# logicBlocks-NOT.net
KiCad netlist of a schematic drawn in EAGLE
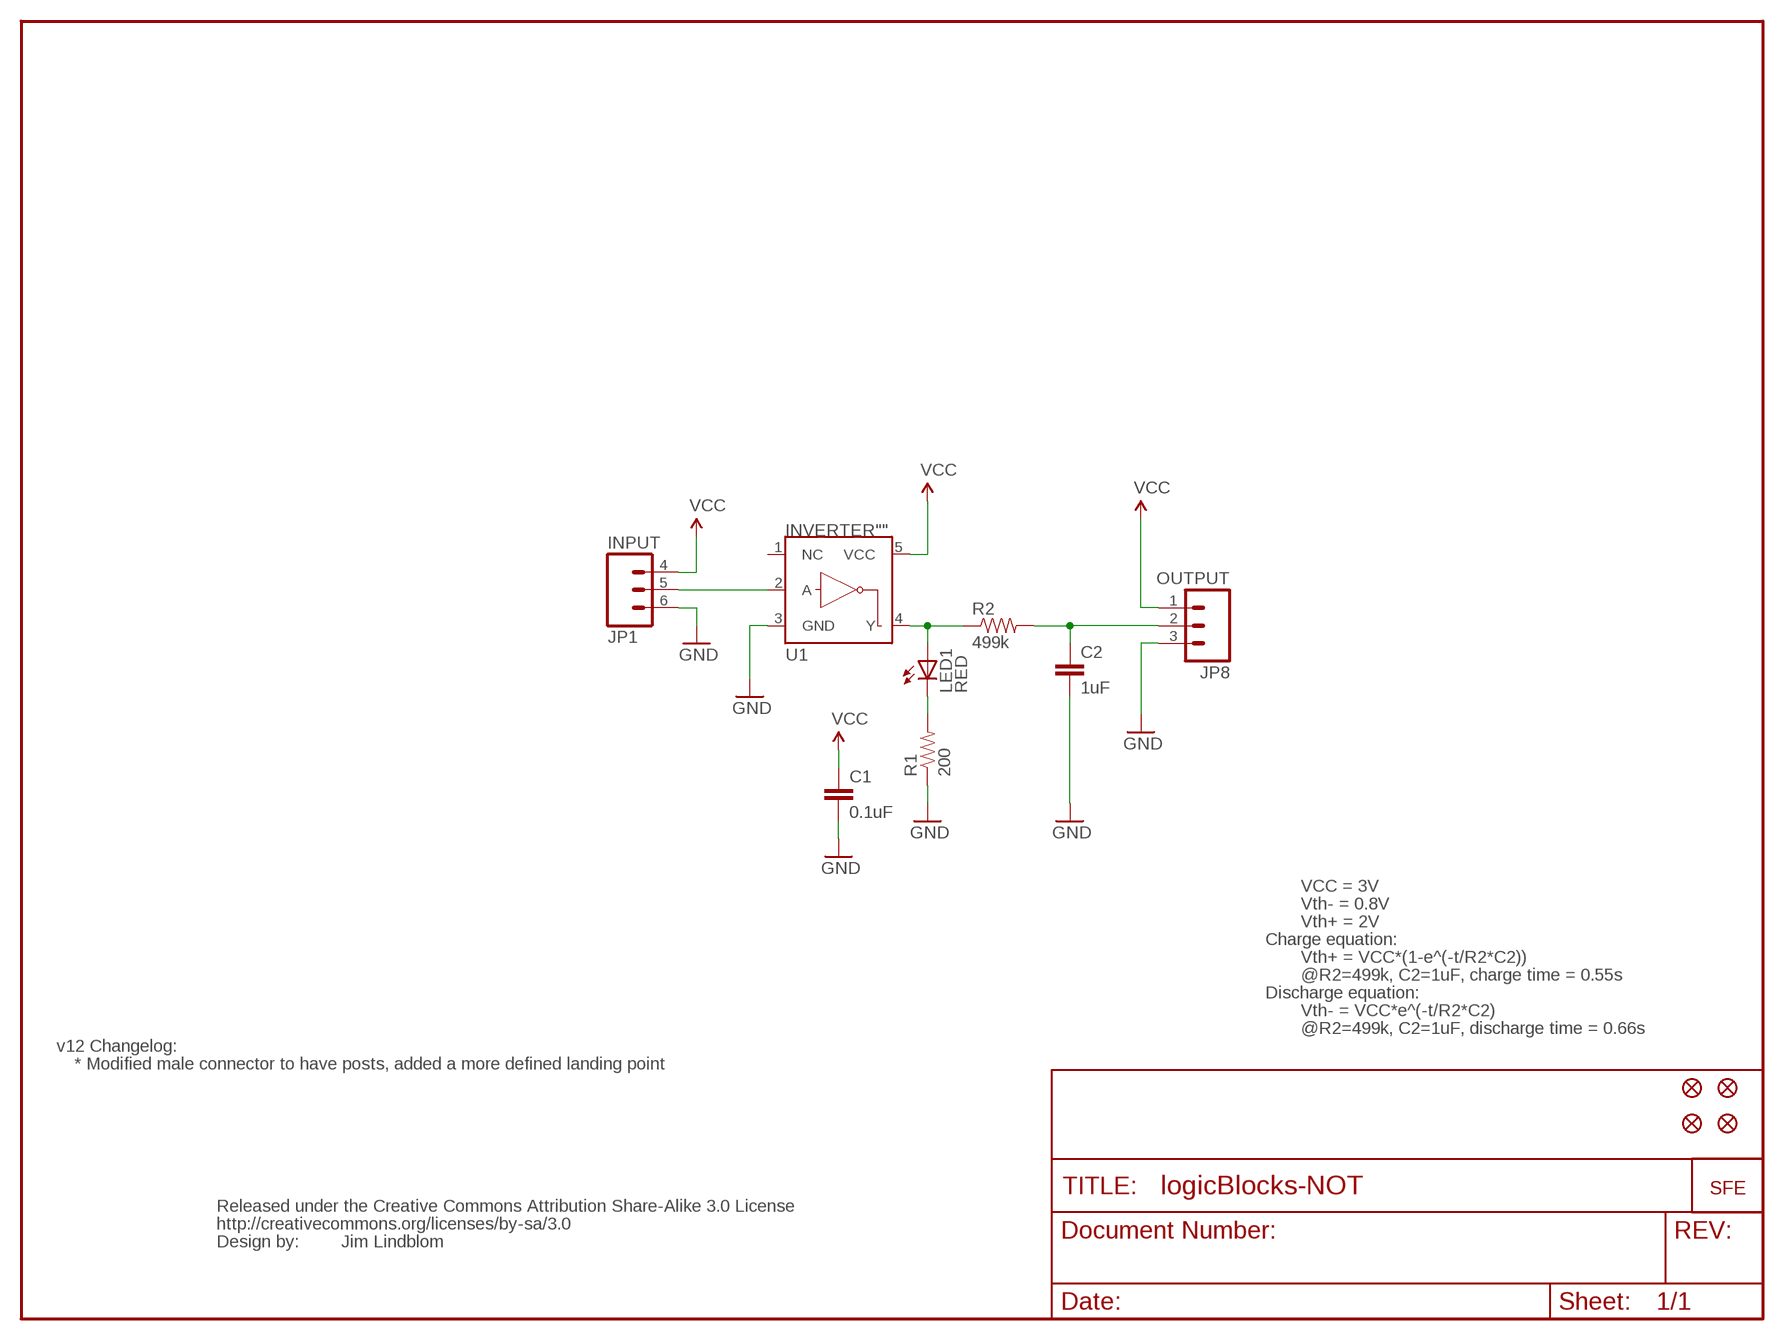
[diagram p0: schematic, sheet 1]

(export (version "E")
  (design (tool "Eeschema 10.0.6"))
  (components
    (comp (ref "C1")
      (value "0.1uF")
      (footprint "eagle-import:0402-CAP")
      (libsource (lib "eagle-import") (part "CAP0402-CAP"))
    )
    (comp (ref "C2")
      (value "1uF")
      (footprint "eagle-import:0402-CAP")
      (libsource (lib "eagle-import") (part "CAP0402-CAP"))
    )
    (comp (ref "FID1")
      (value "FIDUCIAL1X2")
      (footprint "eagle-import:FIDUCIAL-1X2")
      (libsource (lib "eagle-import") (part "FIDUCIAL1X2"))
    )
    (comp (ref "FID2")
      (value "FIDUCIAL1X2")
      (footprint "eagle-import:FIDUCIAL-1X2")
      (libsource (lib "eagle-import") (part "FIDUCIAL1X2"))
    )
    (comp (ref "FID3")
      (value "FIDUCIAL1X2")
      (footprint "eagle-import:FIDUCIAL-1X2")
      (libsource (lib "eagle-import") (part "FIDUCIAL1X2"))
    )
    (comp (ref "FID4")
      (value "FIDUCIAL1X2")
      (footprint "eagle-import:FIDUCIAL-1X2")
      (libsource (lib "eagle-import") (part "FIDUCIAL1X2"))
    )
    (comp (ref "JP1")
      (value "INPUT")
      (footprint "eagle-import:1X03-SMD-FEMALE")
      (libsource (lib "eagle-import") (part "M03SMD-RA-FEMALE"))
    )
    (comp (ref "JP4")
      (value "LOGO-SFESK")
      (footprint "eagle-import:SFE-LOGO-FLAME")
      (libsource (lib "eagle-import") (part "LOGO-SFESK"))
    )
    (comp (ref "JP8")
      (value "OUTPUT")
      (footprint "eagle-import:1X03_SMD_RA_MALE_POST")
      (libsource (lib "eagle-import") (part "M03SMD_RA_MALE_POST"))
    )
    (comp (ref "LED1")
      (value "RED")
      (footprint "eagle-import:LED-1206")
      (libsource (lib "eagle-import") (part "LED1206"))
    )
    (comp (ref "R1")
      (value "200")
      (footprint "eagle-import:0402-RES")
      (libsource (lib "eagle-import") (part "RESISTOR0402-RES"))
    )
    (comp (ref "R2")
      (value "499k")
      (footprint "eagle-import:0402-RES")
      (libsource (lib "eagle-import") (part "RESISTOR0402-RES"))
    )
    (comp (ref "U$2")
      (value "CREATIVE_COMMONS")
      (footprint "eagle-import:CREATIVE_COMMONS")
      (libsource (lib "eagle-import") (part "CREATIVE_COMMONS"))
    )
    (comp (ref "U1")
      (value "INVERTER\"\"")
      (footprint "eagle-import:SC70")
      (libsource (lib "eagle-import") (part "INVERTER{dblquote}{dblquote}"))
    )
  )
  (nets
    (net (code "1") (name "GND") (class "Default")
      (node (ref "C1") (pin "2") (pinfunction "2_2") (pintype "passive"))
      (node (ref "C2") (pin "2") (pinfunction "2_2") (pintype "passive"))
      (node (ref "JP1") (pin "6") (pinfunction "3_6") (pintype "passive"))
      (node (ref "JP8") (pin "3") (pinfunction "3_3") (pintype "passive"))
      (node (ref "R1") (pin "1") (pinfunction "1_1") (pintype "passive"))
      (node (ref "U1") (pin "3") (pinfunction "GND_3") (pintype "bidirectional"))
    )
    (net (code "2") (name "Net-(C2-Pad1)") (class "Default")
      (node (ref "C2") (pin "1") (pinfunction "1_1") (pintype "passive"))
      (node (ref "JP8") (pin "2") (pinfunction "2_2") (pintype "passive"))
      (node (ref "R2") (pin "2") (pinfunction "2_2") (pintype "passive"))
    )
    (net (code "3") (name "Net-(JP1-2)") (class "Default")
      (node (ref "JP1") (pin "5") (pinfunction "2_5") (pintype "passive"))
      (node (ref "U1") (pin "2") (pinfunction "A_2") (pintype "bidirectional"))
    )
    (net (code "4") (name "Net-(LED1-PadC)") (class "Default")
      (node (ref "LED1") (pin "C") (pinfunction "C_C") (pintype "passive"))
      (node (ref "R1") (pin "2") (pinfunction "2_2") (pintype "passive"))
    )
    (net (code "5") (name "Net-(U1-Y)") (class "Default")
      (node (ref "LED1") (pin "A") (pinfunction "A_A") (pintype "passive"))
      (node (ref "R2") (pin "1") (pinfunction "1_1") (pintype "passive"))
      (node (ref "U1") (pin "4") (pinfunction "Y_4") (pintype "bidirectional"))
    )
    (net (code "6") (name "VCC") (class "Default")
      (node (ref "C1") (pin "1") (pinfunction "1_1") (pintype "passive"))
      (node (ref "JP1") (pin "4") (pinfunction "1_4") (pintype "passive"))
      (node (ref "JP8") (pin "1") (pinfunction "1_1") (pintype "passive"))
      (node (ref "U1") (pin "5") (pinfunction "VCC_5") (pintype "bidirectional"))
    )
    (net (code "7") (name "unconnected-(U1-NC-Pad1)") (class "Default")
      (node (ref "U1") (pin "1") (pinfunction "NC_1") (pintype "bidirectional"))
    )
  )
)
